# SAMV71_Xplained_Ultra_Ethernet.net
KiCad netlist of a schematic drawn in Altium Designer
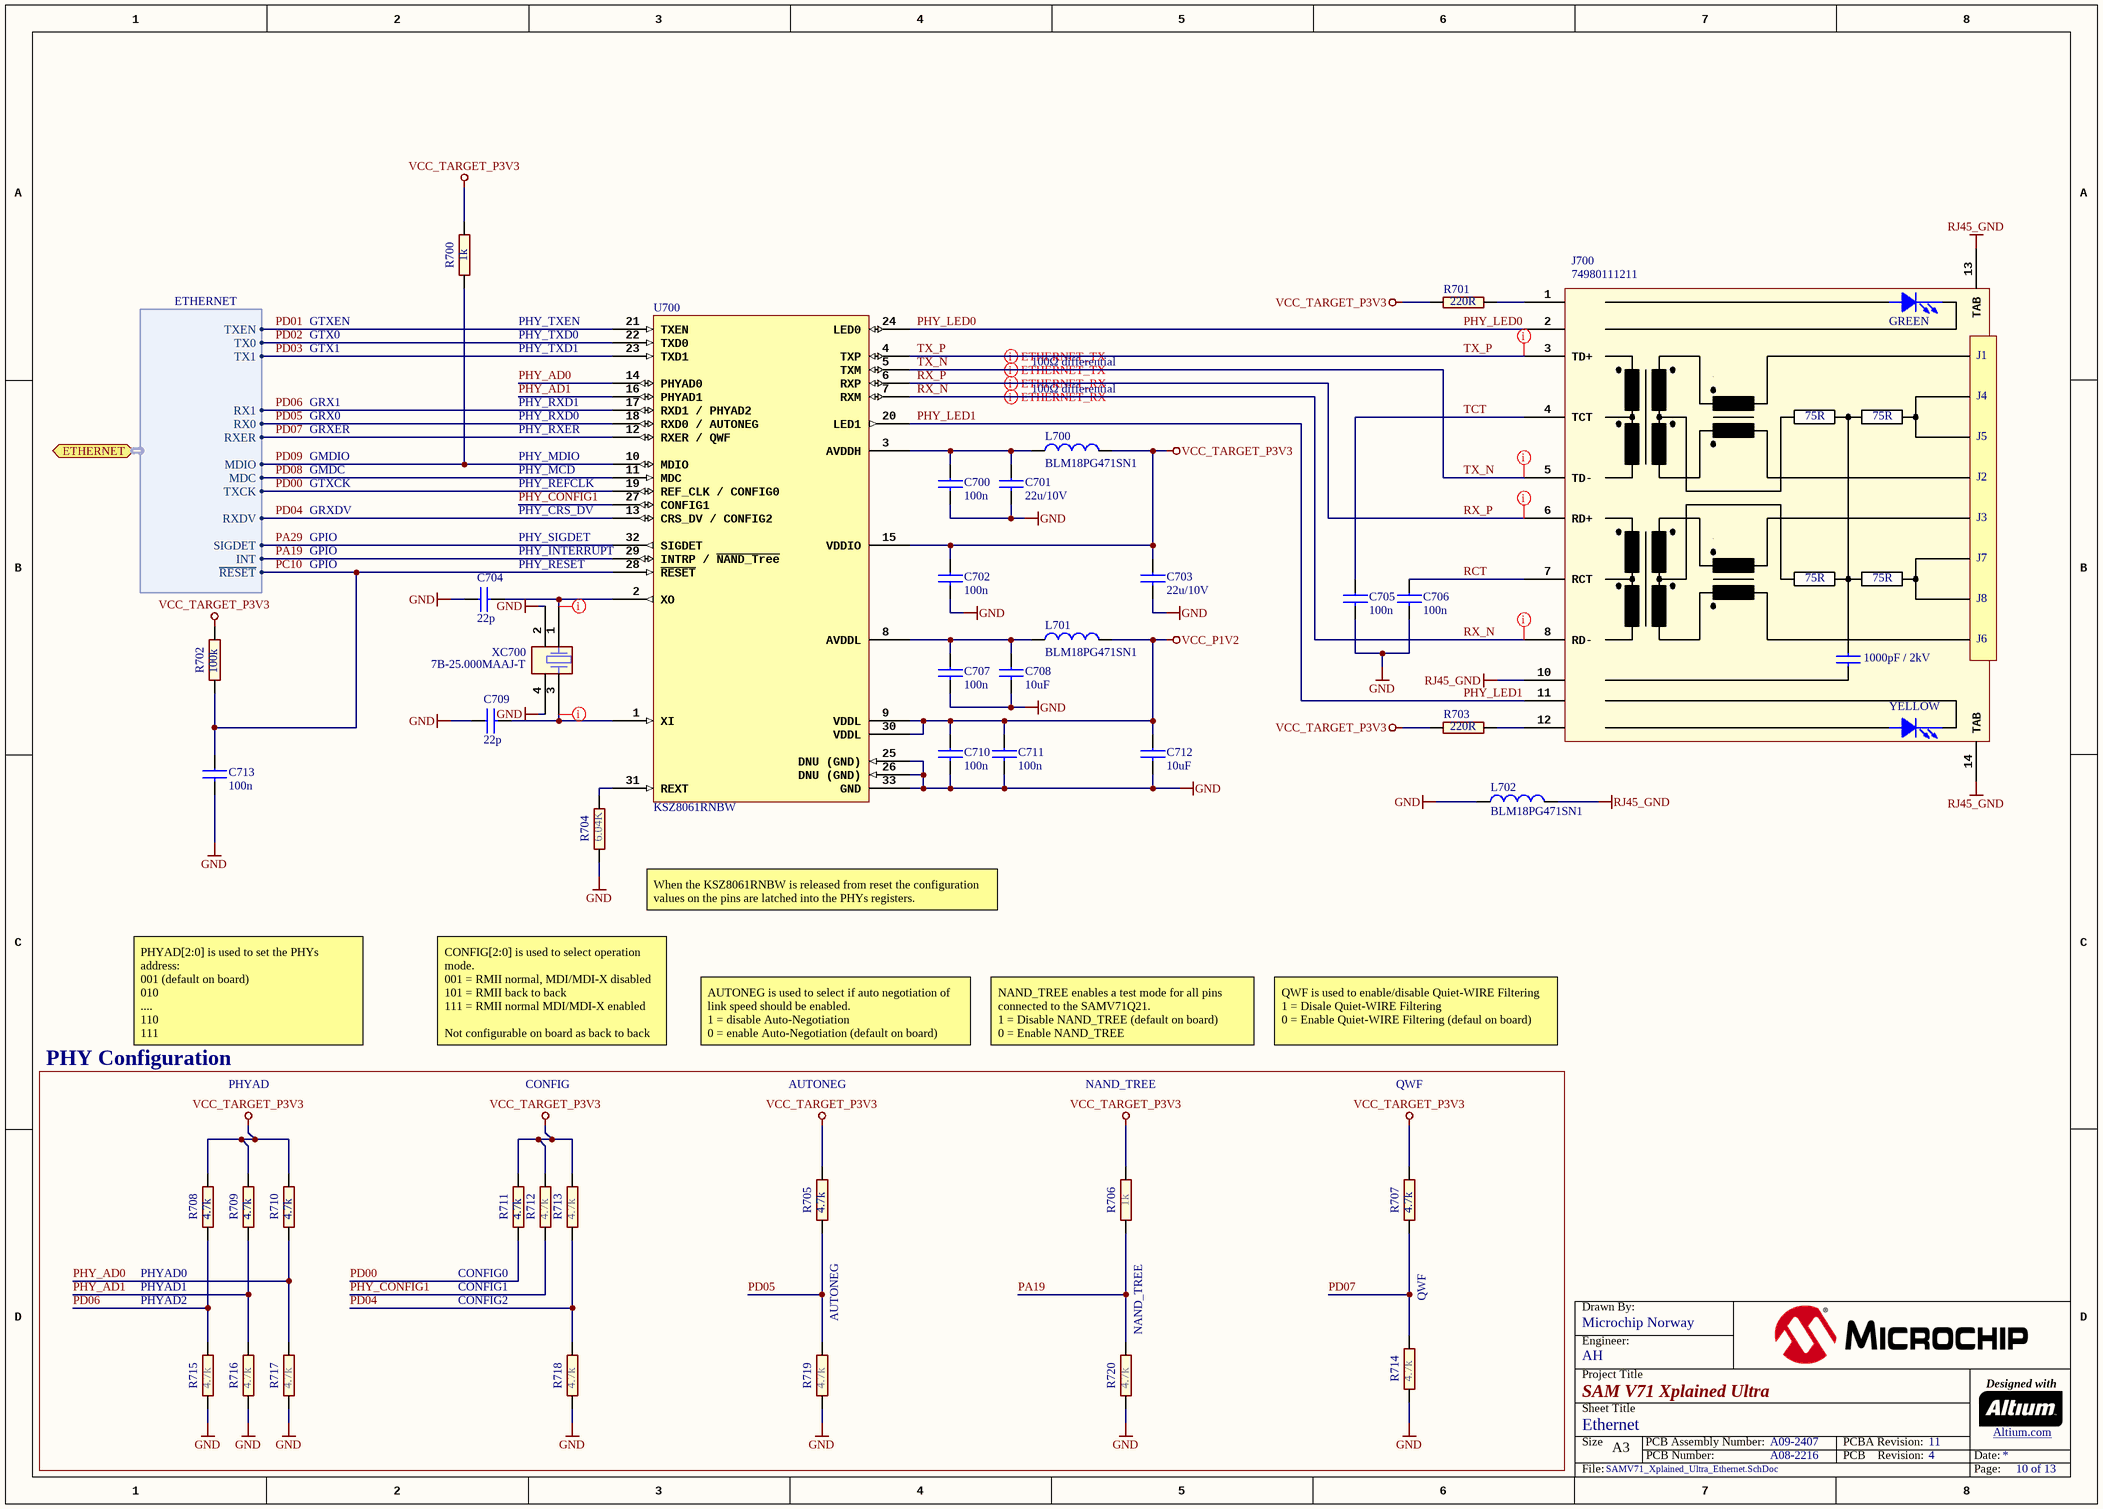
[diagram p0: SAMV71_Xplained_Ultra_Ethernet.SchDoc]

(export (version "E")
  (design (tool "Eeschema 10.0.6"))
  (components
    (comp (ref "C700")
      (value "100n")
      (footprint "AP1-00001")
      (description "Ceramic capacitor, SMD 0402, X7R, 16V, +/-10%")
      (fields (field (name "TOLERANCE") "16V, +/-10%") (field (name "MANUFACTURER") "Kemet"))
      (libsource (lib "AltiumDbLib") (part "CAP-NONPOL"))
    )
    (comp (ref "C701")
      (value "22u/10V")
      (footprint "AP1-00003")
      (description "Ceramic capacitor, SMD 0805, X5R, 10V, ±20%")
      (fields (field (name "MANUFACTURER") "tdk") (field (name "MPN") "C2012X5R1A226M/0.85"))
      (libsource (lib "AltiumDbLib") (part "CAP-NONPOL"))
    )
    (comp (ref "C702")
      (value "100n")
      (footprint "AP1-00001")
      (description "Ceramic capacitor, SMD 0402, X7R, 16V, +/-10%")
      (fields (field (name "TOLERANCE") "16V, +/-10%") (field (name "MANUFACTURER") "Kemet"))
      (libsource (lib "AltiumDbLib") (part "CAP-NONPOL"))
    )
    (comp (ref "C703")
      (value "22u/10V")
      (footprint "AP1-00003")
      (description "Ceramic capacitor, SMD 0805, X5R, 10V, ±20%")
      (fields (field (name "MANUFACTURER") "tdk") (field (name "MPN") "C2012X5R1A226M/0.85"))
      (libsource (lib "AltiumDbLib") (part "CAP-NONPOL"))
    )
    (comp (ref "C704")
      (value "22p")
      (footprint "AP1-00001")
      (description "Ceramic capacitor, SMD 0402, NP0, 50V, +/-5%")
      (fields (field (name "TOLERANCE") "50V, +/-5%") (field (name "MANUFACTURER") "YAGEO CORP"))
      (libsource (lib "AltiumDbLib") (part "CAP-NONPOL"))
    )
    (comp (ref "C705")
      (value "100n")
      (footprint "AP1-00001")
      (description "Ceramic capacitor, SMD 0402, X7R, 16V, +/-10%")
      (fields (field (name "TOLERANCE") "16V, +/-10%") (field (name "MANUFACTURER") "Kemet"))
      (libsource (lib "AltiumDbLib") (part "CAP-NONPOL"))
    )
    (comp (ref "C706")
      (value "100n")
      (footprint "AP1-00001")
      (description "Ceramic capacitor, SMD 0402, X7R, 16V, +/-10%")
      (fields (field (name "TOLERANCE") "16V, +/-10%") (field (name "MANUFACTURER") "Kemet"))
      (libsource (lib "AltiumDbLib") (part "CAP-NONPOL"))
    )
    (comp (ref "C707")
      (value "100n")
      (footprint "AP1-00001")
      (description "Ceramic capacitor, SMD 0402, X7R, 16V, +/-10%")
      (fields (field (name "TOLERANCE") "16V, +/-10%") (field (name "MANUFACTURER") "Kemet"))
      (libsource (lib "AltiumDbLib") (part "CAP-NONPOL"))
    )
    (comp (ref "C708")
      (value "10uF")
      (footprint "AP1-00041")
      (description "Ceramic capacitor, SMD 0805, X7R, 10V, 10 %, (de19441)")
      (fields (field (name "TOLERANCE") "10%") (field (name "MANUFACTURER") "Murata"))
      (libsource (lib "AltiumDbLib") (part "CAP-NONPOL"))
    )
    (comp (ref "C709")
      (value "22p")
      (footprint "AP1-00001")
      (description "Ceramic capacitor, SMD 0402, NP0, 50V, +/-5%")
      (fields (field (name "TOLERANCE") "50V, +/-5%") (field (name "MANUFACTURER") "YAGEO CORP"))
      (libsource (lib "AltiumDbLib") (part "CAP-NONPOL"))
    )
    (comp (ref "C710")
      (value "100n")
      (footprint "AP1-00001")
      (description "Ceramic capacitor, SMD 0402, X7R, 16V, +/-10%")
      (fields (field (name "TOLERANCE") "16V, +/-10%") (field (name "MANUFACTURER") "Kemet"))
      (libsource (lib "AltiumDbLib") (part "CAP-NONPOL"))
    )
    (comp (ref "C711")
      (value "100n")
      (footprint "AP1-00001")
      (description "Ceramic capacitor, SMD 0402, X7R, 16V, +/-10%")
      (fields (field (name "TOLERANCE") "16V, +/-10%") (field (name "MANUFACTURER") "Kemet"))
      (libsource (lib "AltiumDbLib") (part "CAP-NONPOL"))
    )
    (comp (ref "C712")
      (value "10uF")
      (footprint "AP1-00041")
      (description "Ceramic capacitor, SMD 0805, X7R, 10V, 10 %, (de19441)")
      (fields (field (name "TOLERANCE") "10%") (field (name "MANUFACTURER") "Murata"))
      (libsource (lib "AltiumDbLib") (part "CAP-NONPOL"))
    )
    (comp (ref "C713")
      (value "100n")
      (footprint "AP1-00001")
      (description "Ceramic capacitor, SMD 0402, X7R, 16V, +/-10%")
      (fields (field (name "TOLERANCE") "16V, +/-10%") (field (name "MANUFACTURER") "Kemet"))
      (libsource (lib "AltiumDbLib") (part "CAP-NONPOL"))
    )
    (comp (ref "J700")
      (value "74980111211")
      (footprint "AP8-00749")
      (description "10/100Base-TX, SMD, RJ45, green and yellow LEDs, integrated magnetics")
      (fields (field (name "MANUFACTURER") "Wurth Elektronik"))
      (libsource (lib "AltiumDbLib") (part "74980111211"))
    )
    (comp (ref "L700")
      (value "BLM18PG471SN1")
      (footprint "AP3-00005")
      (description "SMD RF inductor 0603. Z=470Ohm (@100MHz), Max R(dc)=0.65Ohm, Max current=1A")
      (fields (field (name "MANUFACTURER") "Murata"))
      (libsource (lib "AltiumDbLib") (part "INDUCTOR"))
    )
    (comp (ref "L701")
      (value "BLM18PG471SN1")
      (footprint "AP3-00005")
      (description "SMD RF inductor 0603. Z=470Ohm (@100MHz), Max R(dc)=0.65Ohm, Max current=1A")
      (fields (field (name "MANUFACTURER") "Murata"))
      (libsource (lib "AltiumDbLib") (part "INDUCTOR"))
    )
    (comp (ref "L702")
      (value "BLM18PG471SN1")
      (footprint "AP3-00005")
      (description "SMD RF inductor 0603. Z=470Ohm (@100MHz), Max R(dc)=0.65Ohm, Max current=1A")
      (fields (field (name "MANUFACTURER") "Murata"))
      (libsource (lib "") (part "INDUCTOR_1"))
    )
    (comp (ref "R700")
      (value "1k")
      (footprint "AP2-00000")
      (description "Thick film resistor, SMD 0402, 1/16W, 1%")
      (fields (field (name "TOLERANCE") "1 %") (field (name "MANUFACTURER") "ASJ"))
      (libsource (lib "") (part "R2_1"))
    )
    (comp (ref "R701")
      (value "220R")
      (footprint "AP2-00000")
      (description "Thick film resistor, SMD 0402, 1/16W, 1%")
      (fields (field (name "TOLERANCE") "1 %") (field (name "MANUFACTURER") "ASJ"))
      (libsource (lib "") (part "R2_3"))
    )
    (comp (ref "R702")
      (value "100k")
      (footprint "AP2-00000")
      (description "Thick film resistor, SMD 0402, 1/16W, 1%")
      (fields (field (name "TOLERANCE") "1 %") (field (name "MANUFACTURER") "ASJ"))
      (libsource (lib "") (part "R2_1"))
    )
    (comp (ref "R703")
      (value "220R")
      (footprint "AP2-00000")
      (description "Thick film resistor, SMD 0402, 1/16W, 1%")
      (fields (field (name "TOLERANCE") "1 %") (field (name "MANUFACTURER") "ASJ"))
      (libsource (lib "") (part "R2_2"))
    )
    (comp (ref "R704")
      (value "6.04K")
      (footprint "AP2-00000")
      (description "Thick film resistor, SMD 0402, 1/16W, 1%, E192")
      (fields (field (name "TOLERANCE") "1%"))
      (libsource (lib "") (part "R2_1"))
    )
    (comp (ref "R705")
      (value "4.7k")
      (footprint "AP2-00000")
      (description "Thick film resistor, SMD 0402, 1/16W, 1%")
      (fields (field (name "TOLERANCE") "1 %") (field (name "MANUFACTURER") "PHYCOMP"))
      (libsource (lib "") (part "R2_1"))
    )
    (comp (ref "R706")
      (value "1k")
      (footprint "AP2-00000")
      (description "Thick film resistor, SMD 0402, 1/16W, 1%")
      (fields (field (name "TOLERANCE") "1 %") (field (name "MANUFACTURER") "ASJ"))
      (libsource (lib "") (part "R2_1"))
    )
    (comp (ref "R707")
      (value "4.7k")
      (footprint "AP2-00000")
      (description "Thick film resistor, SMD 0402, 1/16W, 1%")
      (fields (field (name "TOLERANCE") "1 %") (field (name "MANUFACTURER") "PHYCOMP"))
      (libsource (lib "") (part "R2_1"))
    )
    (comp (ref "R708")
      (value "4.7k")
      (footprint "AP2-00000")
      (description "Thick film resistor, SMD 0402, 1/16W, 1%")
      (fields (field (name "TOLERANCE") "1 %") (field (name "MANUFACTURER") "PHYCOMP"))
      (libsource (lib "") (part "R2_1"))
    )
    (comp (ref "R709")
      (value "4.7k")
      (footprint "AP2-00000")
      (description "Thick film resistor, SMD 0402, 1/16W, 1%")
      (fields (field (name "TOLERANCE") "1 %") (field (name "MANUFACTURER") "PHYCOMP"))
      (libsource (lib "") (part "R2_1"))
    )
    (comp (ref "R710")
      (value "4.7k")
      (footprint "AP2-00000")
      (description "Thick film resistor, SMD 0402, 1/16W, 1%")
      (fields (field (name "TOLERANCE") "1 %") (field (name "MANUFACTURER") "PHYCOMP"))
      (libsource (lib "") (part "R2_1"))
    )
    (comp (ref "R711")
      (value "4.7k")
      (footprint "AP2-00000")
      (description "Thick film resistor, SMD 0402, 1/16W, 1%")
      (fields (field (name "TOLERANCE") "1 %") (field (name "MANUFACTURER") "PHYCOMP"))
      (libsource (lib "") (part "R2_1"))
    )
    (comp (ref "R712")
      (value "4.7k")
      (footprint "AP2-00000")
      (description "Thick film resistor, SMD 0402, 1/16W, 1%")
      (fields (field (name "TOLERANCE") "1 %") (field (name "MANUFACTURER") "PHYCOMP"))
      (libsource (lib "") (part "R2_1"))
    )
    (comp (ref "R713")
      (value "4.7k")
      (footprint "AP2-00000")
      (description "Thick film resistor, SMD 0402, 1/16W, 1%")
      (fields (field (name "TOLERANCE") "1 %") (field (name "MANUFACTURER") "PHYCOMP"))
      (libsource (lib "") (part "R2_1"))
    )
    (comp (ref "R714")
      (value "4.7k")
      (footprint "AP2-00000")
      (description "Thick film resistor, SMD 0402, 1/16W, 1%")
      (fields (field (name "TOLERANCE") "1 %") (field (name "MANUFACTURER") "PHYCOMP"))
      (libsource (lib "AltiumDbLib") (part "R2"))
    )
    (comp (ref "R715")
      (value "4.7k")
      (footprint "AP2-00000")
      (description "Thick film resistor, SMD 0402, 1/16W, 1%")
      (fields (field (name "TOLERANCE") "1 %") (field (name "MANUFACTURER") "PHYCOMP"))
      (libsource (lib "AltiumDbLib") (part "R2"))
    )
    (comp (ref "R716")
      (value "4.7k")
      (footprint "AP2-00000")
      (description "Thick film resistor, SMD 0402, 1/16W, 1%")
      (fields (field (name "TOLERANCE") "1 %") (field (name "MANUFACTURER") "PHYCOMP"))
      (libsource (lib "AltiumDbLib") (part "R2"))
    )
    (comp (ref "R717")
      (value "4.7k")
      (footprint "AP2-00000")
      (description "Thick film resistor, SMD 0402, 1/16W, 1%")
      (fields (field (name "TOLERANCE") "1 %") (field (name "MANUFACTURER") "PHYCOMP"))
      (libsource (lib "AltiumDbLib") (part "R2"))
    )
    (comp (ref "R718")
      (value "4.7k")
      (footprint "AP2-00000")
      (description "Thick film resistor, SMD 0402, 1/16W, 1%")
      (fields (field (name "TOLERANCE") "1 %") (field (name "MANUFACTURER") "PHYCOMP"))
      (libsource (lib "") (part "R2_1"))
    )
    (comp (ref "R719")
      (value "4.7k")
      (footprint "AP2-00000")
      (description "Thick film resistor, SMD 0402, 1/16W, 1%")
      (fields (field (name "TOLERANCE") "1 %") (field (name "MANUFACTURER") "PHYCOMP"))
      (libsource (lib "AltiumDbLib") (part "R2"))
    )
    (comp (ref "R720")
      (value "4.7k")
      (footprint "AP2-00000")
      (description "Thick film resistor, SMD 0402, 1/16W, 1%")
      (fields (field (name "TOLERANCE") "1 %") (field (name "MANUFACTURER") "PHYCOMP"))
      (libsource (lib "AltiumDbLib") (part "R2"))
    )
    (comp (ref "U700")
      (value "KSZ8061RNBW")
      (footprint "AP6-00349")
      (description "10Base-T/100Base-TX PHY, RMII, EEE, 50MHz clock output")
      (fields
        (field (name "MANUFACTURER") "Microchip")
        (field (name "Comment") "Industrial Extended Temperature")
      )
      (libsource (lib "AltiumDbLib") (part "KSZ8061RNB"))
    )
    (comp (ref "XC700")
      (value "7B-25.000MAAJ-T")
      (footprint "AP7-00067")
      (description "25.000 MHz crystal, 18pF, ±30ppm, 5.0 x 3.2 mm")
      (fields (field (name "TOLERANCE") "Â±30ppm") (field (name "MANUFACTURER") "TXC Corporation"))
      (libsource (lib "AltiumDbLib") (part "CRYSTAL1324"))
    )
  )
  (nets
    (net (code "2") (name "/PA19") (class "Default")
      (node (ref "R706") (pin "1") (pinfunction "1_1") (pintype "passive"))
      (node (ref "R720") (pin "1") (pinfunction "1_1") (pintype "passive"))
      (node (ref "U700") (pin "29") (pinfunction "INTRP_/_~{NAND_Tree}_29") (pintype "bidirectional"))
    )
    (net (code "3") (name "/PA29") (class "Default")
      (node (ref "U700") (pin "32") (pinfunction "SIGDET_32") (pintype "output"))
    )
    (net (code "4") (name "/PC10") (class "Default")
      (node (ref "C713") (pin "1") (pinfunction "1_1") (pintype "passive"))
      (node (ref "R702") (pin "1") (pinfunction "1_1") (pintype "passive"))
      (node (ref "U700") (pin "28") (pinfunction "~{RESET}_28") (pintype "input"))
    )
    (net (code "5") (name "/PD00") (class "Default")
      (node (ref "R711") (pin "1") (pinfunction "1_1") (pintype "passive"))
      (node (ref "U700") (pin "19") (pinfunction "REF_CLK_/_CONFIG0_19") (pintype "bidirectional"))
    )
    (net (code "6") (name "/PD01") (class "Default")
      (node (ref "U700") (pin "21") (pinfunction "TXEN_21") (pintype "input"))
    )
    (net (code "7") (name "/PD02") (class "Default")
      (node (ref "U700") (pin "22") (pinfunction "TXD0_22") (pintype "input"))
    )
    (net (code "8") (name "/PD03") (class "Default")
      (node (ref "U700") (pin "23") (pinfunction "TXD1_23") (pintype "input"))
    )
    (net (code "9") (name "/PD04") (class "Default")
      (node (ref "R713") (pin "1") (pinfunction "1_1") (pintype "passive"))
      (node (ref "R718") (pin "2") (pinfunction "2_2") (pintype "passive"))
      (node (ref "U700") (pin "13") (pinfunction "CRS_DV_/_CONFIG2_13") (pintype "bidirectional"))
    )
    (net (code "10") (name "/PD05") (class "Default")
      (node (ref "R705") (pin "1") (pinfunction "1_1") (pintype "passive"))
      (node (ref "R719") (pin "1") (pinfunction "1_1") (pintype "passive"))
      (node (ref "U700") (pin "18") (pinfunction "RXD0_/_AUTONEG_18") (pintype "bidirectional"))
    )
    (net (code "11") (name "/PD06") (class "Default")
      (node (ref "R708") (pin "1") (pinfunction "1_1") (pintype "passive"))
      (node (ref "R715") (pin "1") (pinfunction "1_1") (pintype "passive"))
      (node (ref "U700") (pin "17") (pinfunction "RXD1_/_PHYAD2_17") (pintype "bidirectional"))
    )
    (net (code "12") (name "/PD07") (class "Default")
      (node (ref "R707") (pin "1") (pinfunction "1_1") (pintype "passive"))
      (node (ref "R714") (pin "1") (pinfunction "1_1") (pintype "passive"))
      (node (ref "U700") (pin "12") (pinfunction "RXER_/_QWF_12") (pintype "bidirectional"))
    )
    (net (code "13") (name "/PD08") (class "Default")
      (node (ref "U700") (pin "11") (pinfunction "MDC_11") (pintype "input"))
    )
    (net (code "14") (name "/PD09") (class "Default")
      (node (ref "R700") (pin "1") (pinfunction "1_1") (pintype "passive"))
      (node (ref "U700") (pin "10") (pinfunction "MDIO_10") (pintype "bidirectional"))
    )
    (net (code "15") (name "/PHY_AD0") (class "Default")
      (node (ref "R710") (pin "1") (pinfunction "1_1") (pintype "passive"))
      (node (ref "R717") (pin "1") (pinfunction "1_1") (pintype "passive"))
      (node (ref "U700") (pin "14") (pinfunction "PHYAD0_14") (pintype "bidirectional"))
    )
    (net (code "16") (name "/PHY_AD1") (class "Default")
      (node (ref "R709") (pin "1") (pinfunction "1_1") (pintype "passive"))
      (node (ref "R716") (pin "1") (pinfunction "1_1") (pintype "passive"))
      (node (ref "U700") (pin "16") (pinfunction "PHYAD1_16") (pintype "bidirectional"))
    )
    (net (code "17") (name "/PHY_CONFIG1") (class "Default")
      (node (ref "R712") (pin "1") (pinfunction "1_1") (pintype "passive"))
      (node (ref "U700") (pin "27") (pinfunction "CONFIG1_27") (pintype "bidirectional"))
    )
    (net (code "18") (name "/PHY_LED0") (class "Default")
      (node (ref "J700") (pin "2") (pintype "passive"))
      (node (ref "U700") (pin "24") (pinfunction "LED0_24") (pintype "bidirectional"))
    )
    (net (code "19") (name "/PHY_LED1") (class "Default")
      (node (ref "J700") (pin "11") (pintype "passive"))
      (node (ref "U700") (pin "20") (pinfunction "LED1_20") (pintype "output"))
    )
    (net (code "20") (name "/RCT") (class "Default")
      (node (ref "C706") (pin "1") (pinfunction "1_1") (pintype "passive"))
      (node (ref "J700") (pin "7") (pinfunction "RCT_7") (pintype "passive"))
    )
    (net (code "21") (name "/RX_N") (class "Default")
      (node (ref "J700") (pin "8") (pinfunction "RD-_8") (pintype "passive"))
      (node (ref "U700") (pin "7") (pinfunction "RXM_7") (pintype "bidirectional"))
    )
    (net (code "22") (name "/RX_P") (class "Default")
      (node (ref "J700") (pin "6") (pinfunction "RD+_6") (pintype "passive"))
      (node (ref "U700") (pin "6") (pinfunction "RXP_6") (pintype "bidirectional"))
    )
    (net (code "23") (name "/TCT") (class "Default")
      (node (ref "C705") (pin "1") (pinfunction "1_1") (pintype "passive"))
      (node (ref "J700") (pin "4") (pinfunction "TCT_4") (pintype "passive"))
    )
    (net (code "24") (name "/TX_N") (class "Default")
      (node (ref "J700") (pin "5") (pinfunction "TD-_5") (pintype "passive"))
      (node (ref "U700") (pin "5") (pinfunction "TXM_5") (pintype "bidirectional"))
    )
    (net (code "25") (name "/TX_P") (class "Default")
      (node (ref "J700") (pin "3") (pinfunction "TD+_3") (pintype "passive"))
      (node (ref "U700") (pin "4") (pinfunction "TXP_4") (pintype "bidirectional"))
    )
    (net (code "27") (name "GND") (class "Default")
      (node (ref "C700") (pin "2") (pinfunction "2_2") (pintype "passive"))
      (node (ref "C701") (pin "2") (pinfunction "2_2") (pintype "passive"))
      (node (ref "C702") (pin "2") (pinfunction "2_2") (pintype "passive"))
      (node (ref "C703") (pin "2") (pinfunction "2_2") (pintype "passive"))
      (node (ref "C704") (pin "1") (pinfunction "1_1") (pintype "passive"))
      (node (ref "C705") (pin "2") (pinfunction "2_2") (pintype "passive"))
      (node (ref "C706") (pin "2") (pinfunction "2_2") (pintype "passive"))
      (node (ref "C707") (pin "2") (pinfunction "2_2") (pintype "passive"))
      (node (ref "C708") (pin "2") (pinfunction "2_2") (pintype "passive"))
      (node (ref "C709") (pin "1") (pinfunction "1_1") (pintype "passive"))
      (node (ref "C710") (pin "2") (pinfunction "2_2") (pintype "passive"))
      (node (ref "C711") (pin "2") (pinfunction "2_2") (pintype "passive"))
      (node (ref "C712") (pin "2") (pinfunction "2_2") (pintype "passive"))
      (node (ref "C713") (pin "2") (pinfunction "2_2") (pintype "passive"))
      (node (ref "L702") (pin "1") (pinfunction "1_1") (pintype "passive"))
      (node (ref "R704") (pin "1") (pinfunction "1_1") (pintype "passive"))
      (node (ref "R714") (pin "2") (pinfunction "2_2") (pintype "passive"))
      (node (ref "R715") (pin "2") (pinfunction "2_2") (pintype "passive"))
      (node (ref "R716") (pin "2") (pinfunction "2_2") (pintype "passive"))
      (node (ref "R717") (pin "2") (pinfunction "2_2") (pintype "passive"))
      (node (ref "R718") (pin "1") (pinfunction "1_1") (pintype "passive"))
      (node (ref "R719") (pin "2") (pinfunction "2_2") (pintype "passive"))
      (node (ref "R720") (pin "2") (pinfunction "2_2") (pintype "passive"))
      (node (ref "U700") (pin "25") (pinfunction "DNU_(GND)_25") (pintype "input"))
      (node (ref "U700") (pin "26") (pinfunction "DNU_(GND)_26") (pintype "input"))
      (node (ref "U700") (pin "33") (pinfunction "GND_33") (pintype "power_in"))
      (node (ref "XC700") (pin "2") (pinfunction "2_2") (pintype "passive"))
      (node (ref "XC700") (pin "4") (pinfunction "4_4") (pintype "passive"))
    )
    (net (code "28") (name "Net-(J700-Pad1)") (class "Default")
      (node (ref "J700") (pin "1") (pintype "passive"))
      (node (ref "R701") (pin "1") (pinfunction "1_1") (pintype "passive"))
    )
    (net (code "29") (name "Net-(J700-Pad12)") (class "Default")
      (node (ref "J700") (pin "12") (pintype "passive"))
      (node (ref "R703") (pin "2") (pinfunction "2_2") (pintype "passive"))
    )
    (net (code "30") (name "Net-(U700-AVDDH)") (class "Default")
      (node (ref "C700") (pin "1") (pinfunction "1_1") (pintype "passive"))
      (node (ref "C701") (pin "1") (pinfunction "1_1") (pintype "passive"))
      (node (ref "L700") (pin "2") (pinfunction "2_2") (pintype "passive"))
      (node (ref "U700") (pin "3") (pinfunction "AVDDH_3") (pintype "power_in"))
    )
    (net (code "31") (name "Net-(U700-AVDDL)") (class "Default")
      (node (ref "C707") (pin "1") (pinfunction "1_1") (pintype "passive"))
      (node (ref "C708") (pin "1") (pinfunction "1_1") (pintype "passive"))
      (node (ref "L701") (pin "2") (pinfunction "2_2") (pintype "passive"))
      (node (ref "U700") (pin "8") (pinfunction "AVDDL_8") (pintype "power_in"))
    )
    (net (code "32") (name "Net-(U700-REXT)") (class "Default")
      (node (ref "R704") (pin "2") (pinfunction "2_2") (pintype "passive"))
      (node (ref "U700") (pin "31") (pinfunction "REXT_31") (pintype "input"))
    )
    (net (code "33") (name "Net-(U700-XI)") (class "Default")
      (node (ref "C709") (pin "2") (pinfunction "2_2") (pintype "passive"))
      (node (ref "U700") (pin "1") (pinfunction "XI_1") (pintype "input"))
      (node (ref "XC700") (pin "3") (pinfunction "3_3") (pintype "passive"))
    )
    (net (code "34") (name "Net-(U700-XO)") (class "Default")
      (node (ref "C704") (pin "2") (pinfunction "2_2") (pintype "passive"))
      (node (ref "U700") (pin "2") (pinfunction "XO_2") (pintype "output"))
      (node (ref "XC700") (pin "1") (pinfunction "1_1") (pintype "passive"))
    )
    (net (code "35") (name "RJ45_GND") (class "Default")
      (node (ref "J700") (pin "10") (pintype "passive"))
      (node (ref "J700") (pin "13") (pinfunction "TAB_13") (pintype "power_in"))
      (node (ref "J700") (pin "14") (pinfunction "TAB_14") (pintype "power_in"))
      (node (ref "L702") (pin "2") (pinfunction "2_2") (pintype "passive"))
    )
    (net (code "36") (name "VCC_P1V2") (class "Default")
      (node (ref "C710") (pin "1") (pinfunction "1_1") (pintype "passive"))
      (node (ref "C711") (pin "1") (pinfunction "1_1") (pintype "passive"))
      (node (ref "C712") (pin "1") (pinfunction "1_1") (pintype "passive"))
      (node (ref "L701") (pin "1") (pinfunction "1_1") (pintype "passive"))
      (node (ref "U700") (pin "30") (pinfunction "VDDL_30") (pintype "power_in"))
      (node (ref "U700") (pin "9") (pinfunction "VDDL_9") (pintype "power_in"))
    )
    (net (code "37") (name "VCC_TARGET_P3V3") (class "Default")
      (node (ref "C702") (pin "1") (pinfunction "1_1") (pintype "passive"))
      (node (ref "C703") (pin "1") (pinfunction "1_1") (pintype "passive"))
      (node (ref "L700") (pin "1") (pinfunction "1_1") (pintype "passive"))
      (node (ref "R700") (pin "2") (pinfunction "2_2") (pintype "passive"))
      (node (ref "R701") (pin "2") (pinfunction "2_2") (pintype "passive"))
      (node (ref "R702") (pin "2") (pinfunction "2_2") (pintype "passive"))
      (node (ref "R703") (pin "1") (pinfunction "1_1") (pintype "passive"))
      (node (ref "R705") (pin "2") (pinfunction "2_2") (pintype "passive"))
      (node (ref "R706") (pin "2") (pinfunction "2_2") (pintype "passive"))
      (node (ref "R707") (pin "2") (pinfunction "2_2") (pintype "passive"))
      (node (ref "R708") (pin "2") (pinfunction "2_2") (pintype "passive"))
      (node (ref "R709") (pin "2") (pinfunction "2_2") (pintype "passive"))
      (node (ref "R710") (pin "2") (pinfunction "2_2") (pintype "passive"))
      (node (ref "R711") (pin "2") (pinfunction "2_2") (pintype "passive"))
      (node (ref "R712") (pin "2") (pinfunction "2_2") (pintype "passive"))
      (node (ref "R713") (pin "2") (pinfunction "2_2") (pintype "passive"))
      (node (ref "U700") (pin "15") (pinfunction "VDDIO_15") (pintype "power_in"))
    )
  )
)
